# Radio.net
KiCad netlist of a schematic drawn in Altium Designer
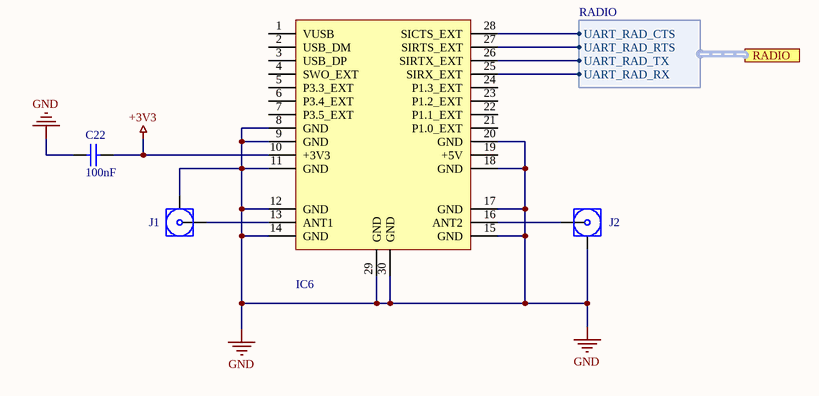
[diagram p0: Radio.SchDoc]

(export (version "E")
  (design (tool "Eeschema 10.0.6"))
  (components
    (comp (ref "C22")
      (value "100nF")
      (footprint "CAPC1608X10N")
      (description "Cap Ceramic 0.1uF 50V X7R 20% SMD 0603 125C T/R")
      (fields (field (name "TOLERANCE") "20%") (field (name "Comment") "C0603C104M5RACTU"))
      (libsource (lib "UWA Aerospace") (part "C0603C104M5RACTU"))
    )
    (comp (ref "IC6")
      (value "RFD900ux")
      (footprint "RFD900ux-Footprint-1")
      (description "Long range surface mount radio module 902-928Mhz")
      (libsource (lib "UWA Aerospace") (part "RFD900ux"))
    )
    (comp (ref "J1")
      (value "PCB.SMAFST.J.A.HT")
      (footprint "PCB.SMAFST.J.A.HT-Footprint-1")
      (description "CONN SMA JACK STR 50OHM PCB")
      (libsource (lib "UWA Aerospace") (part "Connector - Coaxial"))
    )
    (comp (ref "J2")
      (value "PCB.SMAFST.J.A.HT")
      (footprint "PCB.SMAFST.J.A.HT-Footprint-1")
      (description "CONN SMA JACK STR 50OHM PCB")
      (libsource (lib "") (part "Connector - Coaxial_1"))
    )
  )
  (nets
    (net (code "2") (name "+3V3") (class "Default")
      (node (ref "C22") (pin "2") (pinfunction "2_2") (pintype "passive"))
      (node (ref "IC6") (pin "10") (pinfunction "+3V3_10") (pintype "passive"))
    )
    (net (code "3") (name "/UART_RAD_CTS") (class "Default")
      (node (ref "IC6") (pin "28") (pinfunction "SICTS_EXT_28") (pintype "passive"))
    )
    (net (code "4") (name "/UART_RAD_RTS") (class "Default")
      (node (ref "IC6") (pin "27") (pinfunction "SIRTS_EXT_27") (pintype "passive"))
    )
    (net (code "5") (name "/UART_RAD_RX") (class "Default")
      (node (ref "IC6") (pin "25") (pinfunction "SIRX_EXT_25") (pintype "passive"))
    )
    (net (code "6") (name "/UART_RAD_TX") (class "Default")
      (node (ref "IC6") (pin "26") (pinfunction "SIRTX_EXT_26") (pintype "passive"))
    )
    (net (code "8") (name "GND") (class "Default")
      (node (ref "C22") (pin "1") (pinfunction "1_1") (pintype "passive"))
      (node (ref "IC6") (pin "11") (pinfunction "GND_11") (pintype "passive"))
      (node (ref "IC6") (pin "12") (pinfunction "GND_12") (pintype "passive"))
      (node (ref "IC6") (pin "14") (pinfunction "GND_14") (pintype "passive"))
      (node (ref "IC6") (pin "15") (pinfunction "GND_15") (pintype "passive"))
      (node (ref "IC6") (pin "17") (pinfunction "GND_17") (pintype "passive"))
      (node (ref "IC6") (pin "18") (pinfunction "GND_18") (pintype "passive"))
      (node (ref "IC6") (pin "20") (pinfunction "GND_20") (pintype "passive"))
      (node (ref "IC6") (pin "29") (pinfunction "GND_29") (pintype "passive"))
      (node (ref "IC6") (pin "30") (pinfunction "GND_30") (pintype "passive"))
      (node (ref "IC6") (pin "8") (pinfunction "GND_8") (pintype "passive"))
      (node (ref "IC6") (pin "9") (pinfunction "GND_9") (pintype "passive"))
      (node (ref "J1") (pin "2") (pinfunction "GND_2") (pintype "passive"))
      (node (ref "J2") (pin "2") (pinfunction "GND_2") (pintype "passive"))
    )
    (net (code "9") (name "Net-(IC6-ANT1)") (class "Default")
      (node (ref "IC6") (pin "13") (pinfunction "ANT1_13") (pintype "passive"))
      (node (ref "J1") (pin "1") (pinfunction "SIG_1") (pintype "passive"))
    )
    (net (code "10") (name "Net-(IC6-ANT2)") (class "Default")
      (node (ref "IC6") (pin "16") (pinfunction "ANT2_16") (pintype "passive"))
      (node (ref "J2") (pin "1") (pinfunction "SIG_1") (pintype "passive"))
    )
    (net (code "11") (name "unconnected-(IC6-+5V-Pad19)") (class "Default")
      (node (ref "IC6") (pin "19") (pinfunction "+5V_19") (pintype "passive"))
    )
    (net (code "12") (name "unconnected-(IC6-P1.0_EXT-Pad21)") (class "Default")
      (node (ref "IC6") (pin "21") (pinfunction "P1.0_EXT_21") (pintype "passive"))
    )
    (net (code "13") (name "unconnected-(IC6-P1.1_EXT-Pad22)") (class "Default")
      (node (ref "IC6") (pin "22") (pinfunction "P1.1_EXT_22") (pintype "passive"))
    )
    (net (code "14") (name "unconnected-(IC6-P1.2_EXT-Pad23)") (class "Default")
      (node (ref "IC6") (pin "23") (pinfunction "P1.2_EXT_23") (pintype "passive"))
    )
    (net (code "15") (name "unconnected-(IC6-P1.3_EXT-Pad24)") (class "Default")
      (node (ref "IC6") (pin "24") (pinfunction "P1.3_EXT_24") (pintype "passive"))
    )
    (net (code "16") (name "unconnected-(IC6-P3.3_EXT-Pad5)") (class "Default")
      (node (ref "IC6") (pin "5") (pinfunction "P3.3_EXT_5") (pintype "passive"))
    )
    (net (code "17") (name "unconnected-(IC6-P3.4_EXT-Pad6)") (class "Default")
      (node (ref "IC6") (pin "6") (pinfunction "P3.4_EXT_6") (pintype "passive"))
    )
    (net (code "18") (name "unconnected-(IC6-P3.5_EXT-Pad7)") (class "Default")
      (node (ref "IC6") (pin "7") (pinfunction "P3.5_EXT_7") (pintype "passive"))
    )
    (net (code "19") (name "unconnected-(IC6-SWO_EXT-Pad4)") (class "Default")
      (node (ref "IC6") (pin "4") (pinfunction "SWO_EXT_4") (pintype "passive"))
    )
    (net (code "20") (name "unconnected-(IC6-USB_DM-Pad2)") (class "Default")
      (node (ref "IC6") (pin "2") (pinfunction "USB_DM_2") (pintype "passive"))
    )
    (net (code "21") (name "unconnected-(IC6-USB_DP-Pad3)") (class "Default")
      (node (ref "IC6") (pin "3") (pinfunction "USB_DP_3") (pintype "passive"))
    )
    (net (code "22") (name "unconnected-(IC6-VUSB-Pad1)") (class "Default")
      (node (ref "IC6") (pin "1") (pinfunction "VUSB_1") (pintype "passive"))
    )
  )
)
